# drunkGates.net
KiCad netlist of a schematic drawn in EAGLE
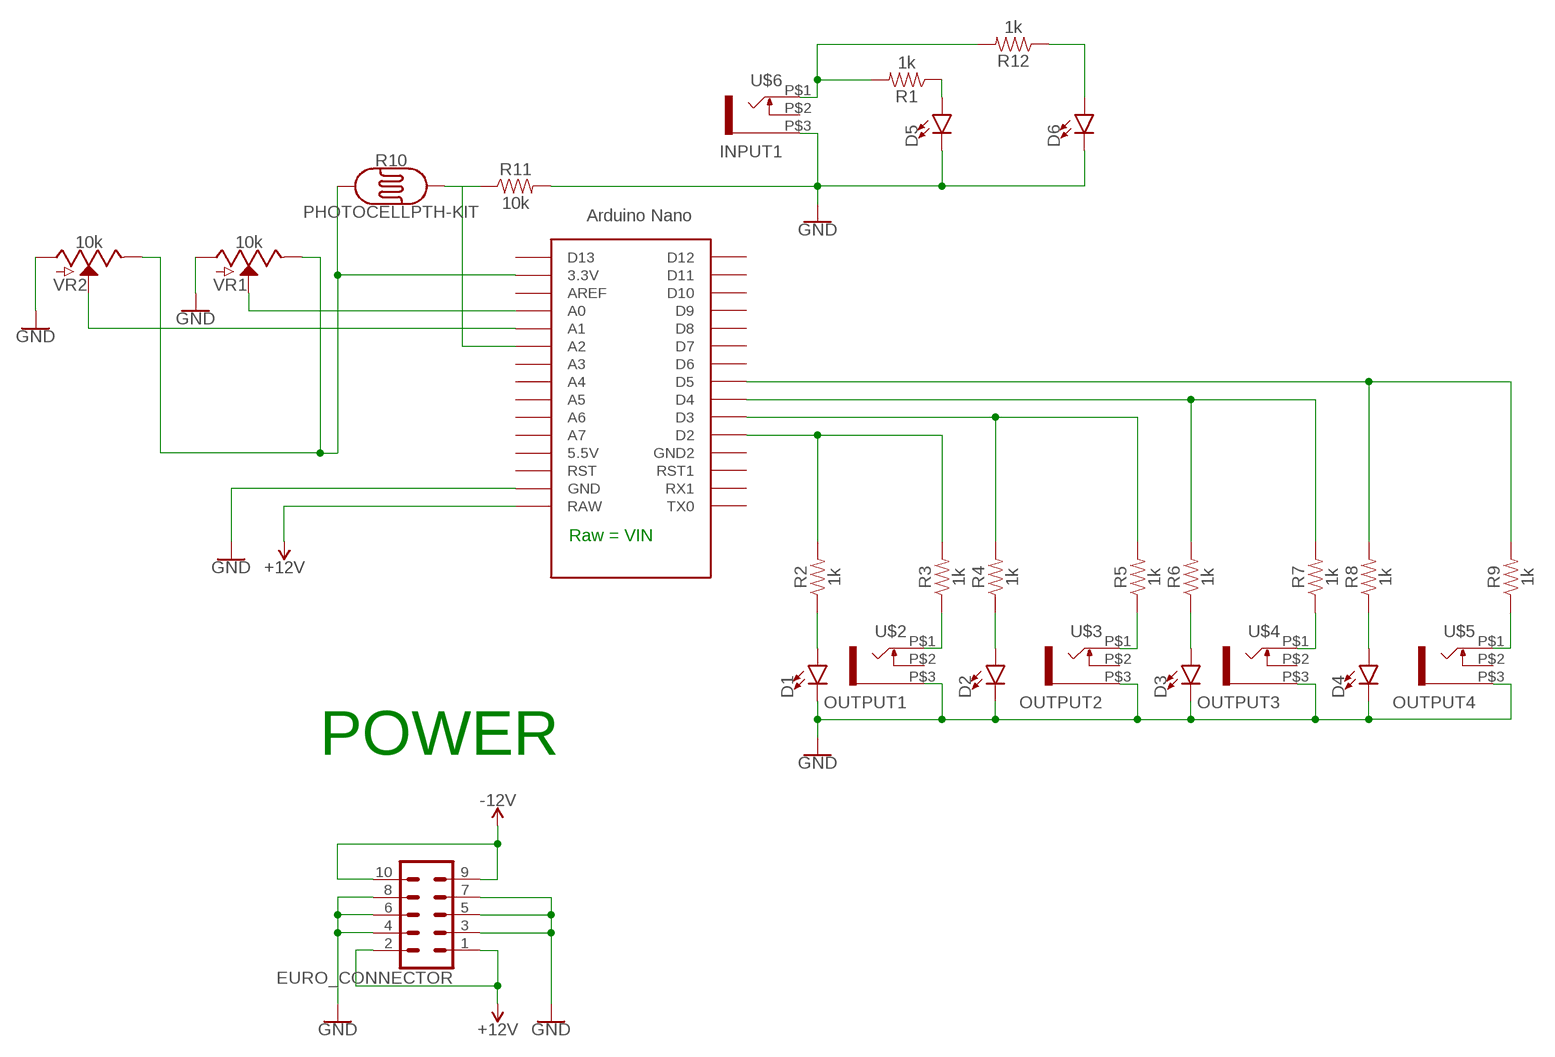
[diagram p0: schematic, sheet 1]

(export (version "E")
  (design (tool "Eeschema 10.0.6"))
  (components
    (comp (ref "D1")
      (value "LED-3MM-NO_SILK")
      (footprint "eagle-import:LED_3MM-NS")
      (libsource (lib "eagle-import") (part "LED-3MM-NO_SILK"))
    )
    (comp (ref "D2")
      (value "LED-3MM-NO_SILK")
      (footprint "eagle-import:LED_3MM-NS")
      (libsource (lib "eagle-import") (part "LED-3MM-NO_SILK"))
    )
    (comp (ref "D3")
      (value "LED-3MM-NO_SILK")
      (footprint "eagle-import:LED_3MM-NS")
      (libsource (lib "eagle-import") (part "LED-3MM-NO_SILK"))
    )
    (comp (ref "D4")
      (value "LED-3MM-NO_SILK")
      (footprint "eagle-import:LED_3MM-NS")
      (libsource (lib "eagle-import") (part "LED-3MM-NO_SILK"))
    )
    (comp (ref "D5")
      (value "LED3MM")
      (footprint "eagle-import:LED_3MM")
      (libsource (lib "eagle-import") (part "LED3MM"))
    )
    (comp (ref "D6")
      (value "LED3MM")
      (footprint "eagle-import:LED_3MM")
      (libsource (lib "eagle-import") (part "LED3MM"))
    )
    (comp (ref "EURO_CONNECTOR")
      (value "CONN_05X2SHD")
      (footprint "eagle-import:2X5-SHROUDED")
      (libsource (lib "eagle-import") (part "CONN_05X2SHD"))
    )
    (comp (ref "R1")
      (value "1k")
      (footprint "eagle-import:AXIAL-0.3")
      (libsource (lib "eagle-import") (part "1KOHM-HORIZ-1/4W-5%"))
    )
    (comp (ref "R2")
      (value "1k")
      (footprint "eagle-import:AXIAL-0.3")
      (libsource (lib "eagle-import") (part "1KOHM-HORIZ-1/4W-5%"))
    )
    (comp (ref "R3")
      (value "1k")
      (footprint "eagle-import:AXIAL-0.3")
      (libsource (lib "eagle-import") (part "1KOHM-HORIZ-1/4W-5%"))
    )
    (comp (ref "R4")
      (value "1k")
      (footprint "eagle-import:AXIAL-0.3")
      (libsource (lib "eagle-import") (part "1KOHM-HORIZ-1/4W-5%"))
    )
    (comp (ref "R5")
      (value "1k")
      (footprint "eagle-import:AXIAL-0.3")
      (libsource (lib "eagle-import") (part "1KOHM-HORIZ-1/4W-5%"))
    )
    (comp (ref "R6")
      (value "1k")
      (footprint "eagle-import:AXIAL-0.3")
      (libsource (lib "eagle-import") (part "1KOHM-HORIZ-1/4W-5%"))
    )
    (comp (ref "R7")
      (value "1k")
      (footprint "eagle-import:AXIAL-0.3")
      (libsource (lib "eagle-import") (part "1KOHM-HORIZ-1/4W-5%"))
    )
    (comp (ref "R8")
      (value "1k")
      (footprint "eagle-import:AXIAL-0.3")
      (libsource (lib "eagle-import") (part "1KOHM-HORIZ-1/4W-5%"))
    )
    (comp (ref "R9")
      (value "1k")
      (footprint "eagle-import:AXIAL-0.3")
      (libsource (lib "eagle-import") (part "1KOHM-HORIZ-1/4W-5%"))
    )
    (comp (ref "R10")
      (value "PHOTOCELLPTH-KIT")
      (footprint "eagle-import:PHOTOCELL-KIT")
      (libsource (lib "eagle-import") (part "PHOTOCELLPTH-KIT"))
    )
    (comp (ref "R11")
      (value "10k")
      (footprint "eagle-import:AXIAL-0.3")
      (libsource (lib "eagle-import") (part "1KOHM-HORIZ-1/4W-5%"))
    )
    (comp (ref "R12")
      (value "1k")
      (footprint "eagle-import:AXIAL-0.3")
      (libsource (lib "eagle-import") (part "1KOHM-HORIZ-1/4W-5%"))
    )
    (comp (ref "U$1")
      (value "NANO")
      (footprint "eagle-import:NANO")
      (libsource (lib "eagle-import") (part "NANO"))
    )
    (comp (ref "U$2")
      (value "OUTPUT1")
      (footprint "eagle-import:WQP-PJ301M-12_JACK")
      (libsource (lib "eagle-import") (part "WQP-PJ301M-12_JACK"))
    )
    (comp (ref "U$3")
      (value "OUTPUT2")
      (footprint "eagle-import:WQP-PJ301M-12_JACK")
      (libsource (lib "eagle-import") (part "WQP-PJ301M-12_JACK"))
    )
    (comp (ref "U$4")
      (value "OUTPUT3")
      (footprint "eagle-import:WQP-PJ301M-12_JACK")
      (libsource (lib "eagle-import") (part "WQP-PJ301M-12_JACK"))
    )
    (comp (ref "U$5")
      (value "OUTPUT4")
      (footprint "eagle-import:WQP-PJ301M-12_JACK")
      (libsource (lib "eagle-import") (part "WQP-PJ301M-12_JACK"))
    )
    (comp (ref "U$6")
      (value "INPUT1")
      (footprint "eagle-import:WQP-PJ301M-12_JACK")
      (libsource (lib "eagle-import") (part "WQP-PJ301M-12_JACK"))
    )
    (comp (ref "VR1")
      (value "10k")
      (footprint "eagle-import:POT-PTH-ALPS")
      (libsource (lib "eagle-import") (part "POTENTIOMETER-PTH-9MM-1/20W-20%"))
    )
    (comp (ref "VR2")
      (value "10k")
      (footprint "eagle-import:POT-PTH-ALPS")
      (libsource (lib "eagle-import") (part "POTENTIOMETER-PTH-9MM-1/20W-20%"))
    )
  )
  (nets
    (net (code "1") (name "+12V") (class "Default")
      (node (ref "EURO_CONNECTOR") (pin "1") (pinfunction "1_1") (pintype "passive"))
      (node (ref "EURO_CONNECTOR") (pin "2") (pinfunction "2_2") (pintype "passive"))
      (node (ref "U$1") (pin "RAW") (pinfunction "RAW_RAW") (pintype "bidirectional"))
    )
    (net (code "2") (name "-12V") (class "Default")
      (node (ref "EURO_CONNECTOR") (pin "10") (pinfunction "10_10") (pintype "passive"))
      (node (ref "EURO_CONNECTOR") (pin "9") (pinfunction "9_9") (pintype "passive"))
    )
    (net (code "3") (name "GND") (class "Default")
      (node (ref "D1") (pin "K") (pinfunction "C_K") (pintype "passive"))
      (node (ref "D2") (pin "K") (pinfunction "C_K") (pintype "passive"))
      (node (ref "D3") (pin "K") (pinfunction "C_K") (pintype "passive"))
      (node (ref "D4") (pin "K") (pinfunction "C_K") (pintype "passive"))
      (node (ref "D5") (pin "K") (pinfunction "C_K") (pintype "passive"))
      (node (ref "D6") (pin "K") (pinfunction "C_K") (pintype "passive"))
      (node (ref "EURO_CONNECTOR") (pin "3") (pinfunction "3_3") (pintype "passive"))
      (node (ref "EURO_CONNECTOR") (pin "4") (pinfunction "4_4") (pintype "passive"))
      (node (ref "EURO_CONNECTOR") (pin "5") (pinfunction "5_5") (pintype "passive"))
      (node (ref "EURO_CONNECTOR") (pin "6") (pinfunction "6_6") (pintype "passive"))
      (node (ref "EURO_CONNECTOR") (pin "7") (pinfunction "7_7") (pintype "passive"))
      (node (ref "EURO_CONNECTOR") (pin "8") (pinfunction "8_8") (pintype "passive"))
      (node (ref "R11") (pin "P$2") (pinfunction "2_P$2") (pintype "passive"))
      (node (ref "U$1") (pin "GND") (pinfunction "GND_GND") (pintype "bidirectional"))
      (node (ref "U$2") (pin "P$3") (pinfunction "1_P$3") (pintype "passive"))
      (node (ref "U$3") (pin "P$3") (pinfunction "1_P$3") (pintype "passive"))
      (node (ref "U$4") (pin "P$3") (pinfunction "1_P$3") (pintype "passive"))
      (node (ref "U$5") (pin "P$3") (pinfunction "1_P$3") (pintype "passive"))
      (node (ref "U$6") (pin "P$3") (pinfunction "1_P$3") (pintype "passive"))
      (node (ref "VR1") (pin "P$3") (pinfunction "A_P$3") (pintype "passive"))
      (node (ref "VR2") (pin "P$3") (pinfunction "A_P$3") (pintype "passive"))
    )
    (net (code "4") (name "Net-(R1-1)") (class "Default")
      (node (ref "D5") (pin "A") (pinfunction "A_A") (pintype "passive"))
      (node (ref "R1") (pin "P$1") (pinfunction "1_P$1") (pintype "passive"))
    )
    (net (code "5") (name "Net-(R1-2)") (class "Default")
      (node (ref "R1") (pin "P$2") (pinfunction "2_P$2") (pintype "passive"))
      (node (ref "R12") (pin "P$2") (pinfunction "2_P$2") (pintype "passive"))
      (node (ref "U$6") (pin "P$1") (pinfunction "2_P$1") (pintype "passive"))
    )
    (net (code "6") (name "Net-(R2-1)") (class "Default")
      (node (ref "D1") (pin "A") (pinfunction "A_A") (pintype "passive"))
      (node (ref "R2") (pin "P$1") (pinfunction "1_P$1") (pintype "passive"))
    )
    (net (code "7") (name "Net-(R2-2)") (class "Default")
      (node (ref "R2") (pin "P$2") (pinfunction "2_P$2") (pintype "passive"))
      (node (ref "R3") (pin "P$2") (pinfunction "2_P$2") (pintype "passive"))
      (node (ref "U$1") (pin "D2") (pinfunction "D2_D2") (pintype "bidirectional"))
    )
    (net (code "8") (name "Net-(R3-1)") (class "Default")
      (node (ref "R3") (pin "P$1") (pinfunction "1_P$1") (pintype "passive"))
      (node (ref "U$2") (pin "P$1") (pinfunction "2_P$1") (pintype "passive"))
    )
    (net (code "9") (name "Net-(R4-1)") (class "Default")
      (node (ref "D2") (pin "A") (pinfunction "A_A") (pintype "passive"))
      (node (ref "R4") (pin "P$1") (pinfunction "1_P$1") (pintype "passive"))
    )
    (net (code "10") (name "Net-(R4-2)") (class "Default")
      (node (ref "R4") (pin "P$2") (pinfunction "2_P$2") (pintype "passive"))
      (node (ref "R5") (pin "P$2") (pinfunction "2_P$2") (pintype "passive"))
      (node (ref "U$1") (pin "D3") (pinfunction "D3_D3") (pintype "bidirectional"))
    )
    (net (code "11") (name "Net-(R5-1)") (class "Default")
      (node (ref "R5") (pin "P$1") (pinfunction "1_P$1") (pintype "passive"))
      (node (ref "U$3") (pin "P$1") (pinfunction "2_P$1") (pintype "passive"))
    )
    (net (code "12") (name "Net-(R6-1)") (class "Default")
      (node (ref "D3") (pin "A") (pinfunction "A_A") (pintype "passive"))
      (node (ref "R6") (pin "P$1") (pinfunction "1_P$1") (pintype "passive"))
    )
    (net (code "13") (name "Net-(R6-2)") (class "Default")
      (node (ref "R6") (pin "P$2") (pinfunction "2_P$2") (pintype "passive"))
      (node (ref "R7") (pin "P$2") (pinfunction "2_P$2") (pintype "passive"))
      (node (ref "U$1") (pin "D4") (pinfunction "D4_D4") (pintype "bidirectional"))
    )
    (net (code "14") (name "Net-(R7-1)") (class "Default")
      (node (ref "R7") (pin "P$1") (pinfunction "1_P$1") (pintype "passive"))
      (node (ref "U$4") (pin "P$1") (pinfunction "2_P$1") (pintype "passive"))
    )
    (net (code "15") (name "Net-(R8-1)") (class "Default")
      (node (ref "D4") (pin "A") (pinfunction "A_A") (pintype "passive"))
      (node (ref "R8") (pin "P$1") (pinfunction "1_P$1") (pintype "passive"))
    )
    (net (code "16") (name "Net-(R8-2)") (class "Default")
      (node (ref "R8") (pin "P$2") (pinfunction "2_P$2") (pintype "passive"))
      (node (ref "R9") (pin "P$2") (pinfunction "2_P$2") (pintype "passive"))
      (node (ref "U$1") (pin "D5") (pinfunction "D5_D5") (pintype "bidirectional"))
    )
    (net (code "17") (name "Net-(R9-1)") (class "Default")
      (node (ref "R9") (pin "P$1") (pinfunction "1_P$1") (pintype "passive"))
      (node (ref "U$5") (pin "P$1") (pinfunction "2_P$1") (pintype "passive"))
    )
    (net (code "18") (name "Net-(R10-P$1)") (class "Default")
      (node (ref "R10") (pin "1") (pinfunction "P$1_1") (pintype "bidirectional"))
      (node (ref "U$1") (pin "3.3V") (pinfunction "3.3V_3.3V") (pintype "bidirectional"))
      (node (ref "VR1") (pin "P$1") (pinfunction "E_P$1") (pintype "passive"))
      (node (ref "VR2") (pin "P$1") (pinfunction "E_P$1") (pintype "passive"))
    )
    (net (code "19") (name "Net-(R10-P$2)") (class "Default")
      (node (ref "R10") (pin "2") (pinfunction "P$2_2") (pintype "bidirectional"))
      (node (ref "R11") (pin "P$1") (pinfunction "1_P$1") (pintype "passive"))
      (node (ref "U$1") (pin "A2") (pinfunction "A2_A2") (pintype "bidirectional"))
    )
    (net (code "20") (name "Net-(R12-1)") (class "Default")
      (node (ref "D6") (pin "A") (pinfunction "A_A") (pintype "passive"))
      (node (ref "R12") (pin "P$1") (pinfunction "1_P$1") (pintype "passive"))
    )
    (net (code "21") (name "Net-(VR1-S)") (class "Default")
      (node (ref "U$1") (pin "A0") (pinfunction "A0_A0") (pintype "bidirectional"))
      (node (ref "VR1") (pin "P$2") (pinfunction "S_P$2") (pintype "passive"))
    )
    (net (code "22") (name "Net-(VR2-S)") (class "Default")
      (node (ref "U$1") (pin "A1") (pinfunction "A1_A1") (pintype "bidirectional"))
      (node (ref "VR2") (pin "P$2") (pinfunction "S_P$2") (pintype "passive"))
    )
    (net (code "23") (name "unconnected-(U$1-5.5V-Pad5V)") (class "Default")
      (node (ref "U$1") (pin "5V") (pinfunction "5.5V_5V") (pintype "bidirectional"))
    )
    (net (code "24") (name "unconnected-(U$1-GND2-PadGND1)") (class "Default")
      (node (ref "U$1") (pin "GND1") (pinfunction "GND2_GND1") (pintype "bidirectional"))
    )
    (net (code "25") (name "unconnected-(U$1-PadA3)") (class "Default")
      (node (ref "U$1") (pin "A3") (pinfunction "A3_A3") (pintype "bidirectional"))
    )
    (net (code "26") (name "unconnected-(U$1-PadA4)") (class "Default")
      (node (ref "U$1") (pin "A4") (pinfunction "A4_A4") (pintype "bidirectional"))
    )
    (net (code "27") (name "unconnected-(U$1-PadA5)") (class "Default")
      (node (ref "U$1") (pin "A5") (pinfunction "A5_A5") (pintype "bidirectional"))
    )
    (net (code "28") (name "unconnected-(U$1-PadA6)") (class "Default")
      (node (ref "U$1") (pin "A6") (pinfunction "A6_A6") (pintype "bidirectional"))
    )
    (net (code "29") (name "unconnected-(U$1-PadA7)") (class "Default")
      (node (ref "U$1") (pin "A7") (pinfunction "A7_A7") (pintype "bidirectional"))
    )
    (net (code "30") (name "unconnected-(U$1-PadAREF)") (class "Default")
      (node (ref "U$1") (pin "AREF") (pinfunction "AREF_AREF") (pintype "bidirectional"))
    )
    (net (code "31") (name "unconnected-(U$1-PadD6)") (class "Default")
      (node (ref "U$1") (pin "D6") (pinfunction "D6_D6") (pintype "bidirectional"))
    )
    (net (code "32") (name "unconnected-(U$1-PadD7)") (class "Default")
      (node (ref "U$1") (pin "D7") (pinfunction "D7_D7") (pintype "bidirectional"))
    )
    (net (code "33") (name "unconnected-(U$1-PadD8)") (class "Default")
      (node (ref "U$1") (pin "D8") (pinfunction "D8_D8") (pintype "bidirectional"))
    )
    (net (code "34") (name "unconnected-(U$1-PadD9)") (class "Default")
      (node (ref "U$1") (pin "D9") (pinfunction "D9_D9") (pintype "bidirectional"))
    )
    (net (code "35") (name "unconnected-(U$1-PadD10)") (class "Default")
      (node (ref "U$1") (pin "D10") (pinfunction "D10_D10") (pintype "bidirectional"))
    )
    (net (code "36") (name "unconnected-(U$1-PadD11)") (class "Default")
      (node (ref "U$1") (pin "D11") (pinfunction "D11_D11") (pintype "bidirectional"))
    )
    (net (code "37") (name "unconnected-(U$1-PadD12)") (class "Default")
      (node (ref "U$1") (pin "D12") (pinfunction "D12_D12") (pintype "bidirectional"))
    )
    (net (code "38") (name "unconnected-(U$1-PadD13)") (class "Default")
      (node (ref "U$1") (pin "D13") (pinfunction "D13_D13") (pintype "bidirectional"))
    )
    (net (code "39") (name "unconnected-(U$1-PadICSP1)") (class "Default")
      (node (ref "U$1") (pin "ICSP1") (pinfunction "ICSP1_ICSP1") (pintype "bidirectional"))
    )
    (net (code "40") (name "unconnected-(U$1-PadICSP2)") (class "Default")
      (node (ref "U$1") (pin "ICSP2") (pinfunction "ICSP2_ICSP2") (pintype "bidirectional"))
    )
    (net (code "41") (name "unconnected-(U$1-PadICSP3)") (class "Default")
      (node (ref "U$1") (pin "ICSP3") (pinfunction "ICSP3_ICSP3") (pintype "bidirectional"))
    )
    (net (code "42") (name "unconnected-(U$1-PadICSP4)") (class "Default")
      (node (ref "U$1") (pin "ICSP4") (pinfunction "ICSP4_ICSP4") (pintype "bidirectional"))
    )
    (net (code "43") (name "unconnected-(U$1-PadICSP5)") (class "Default")
      (node (ref "U$1") (pin "ICSP5") (pinfunction "ICSP5_ICSP5") (pintype "bidirectional"))
    )
    (net (code "44") (name "unconnected-(U$1-PadICSP6)") (class "Default")
      (node (ref "U$1") (pin "ICSP6") (pinfunction "ICSP6_ICSP6") (pintype "bidirectional"))
    )
    (net (code "45") (name "unconnected-(U$1-PadRST)") (class "Default")
      (node (ref "U$1") (pin "RST") (pinfunction "RST_RST") (pintype "bidirectional"))
    )
    (net (code "46") (name "unconnected-(U$1-PadRST1)") (class "Default")
      (node (ref "U$1") (pin "RST1") (pinfunction "RST1_RST1") (pintype "bidirectional"))
    )
    (net (code "47") (name "unconnected-(U$1-PadRX1)") (class "Default")
      (node (ref "U$1") (pin "RX1") (pinfunction "RX1_RX1") (pintype "bidirectional"))
    )
    (net (code "48") (name "unconnected-(U$1-PadTX0)") (class "Default")
      (node (ref "U$1") (pin "TX0") (pinfunction "TX0_TX0") (pintype "bidirectional"))
    )
    (net (code "49") (name "unconnected-(U$2-3-PadP$2)") (class "Default")
      (node (ref "U$2") (pin "P$2") (pinfunction "3_P$2") (pintype "passive"))
    )
    (net (code "50") (name "unconnected-(U$3-3-PadP$2)") (class "Default")
      (node (ref "U$3") (pin "P$2") (pinfunction "3_P$2") (pintype "passive"))
    )
    (net (code "51") (name "unconnected-(U$4-3-PadP$2)") (class "Default")
      (node (ref "U$4") (pin "P$2") (pinfunction "3_P$2") (pintype "passive"))
    )
    (net (code "52") (name "unconnected-(U$5-3-PadP$2)") (class "Default")
      (node (ref "U$5") (pin "P$2") (pinfunction "3_P$2") (pintype "passive"))
    )
    (net (code "53") (name "unconnected-(U$6-3-PadP$2)") (class "Default")
      (node (ref "U$6") (pin "P$2") (pinfunction "3_P$2") (pintype "passive"))
    )
  )
)
